# stm32h750xbh6-sig.net
KiCad netlist of a schematic drawn in Altium Designer
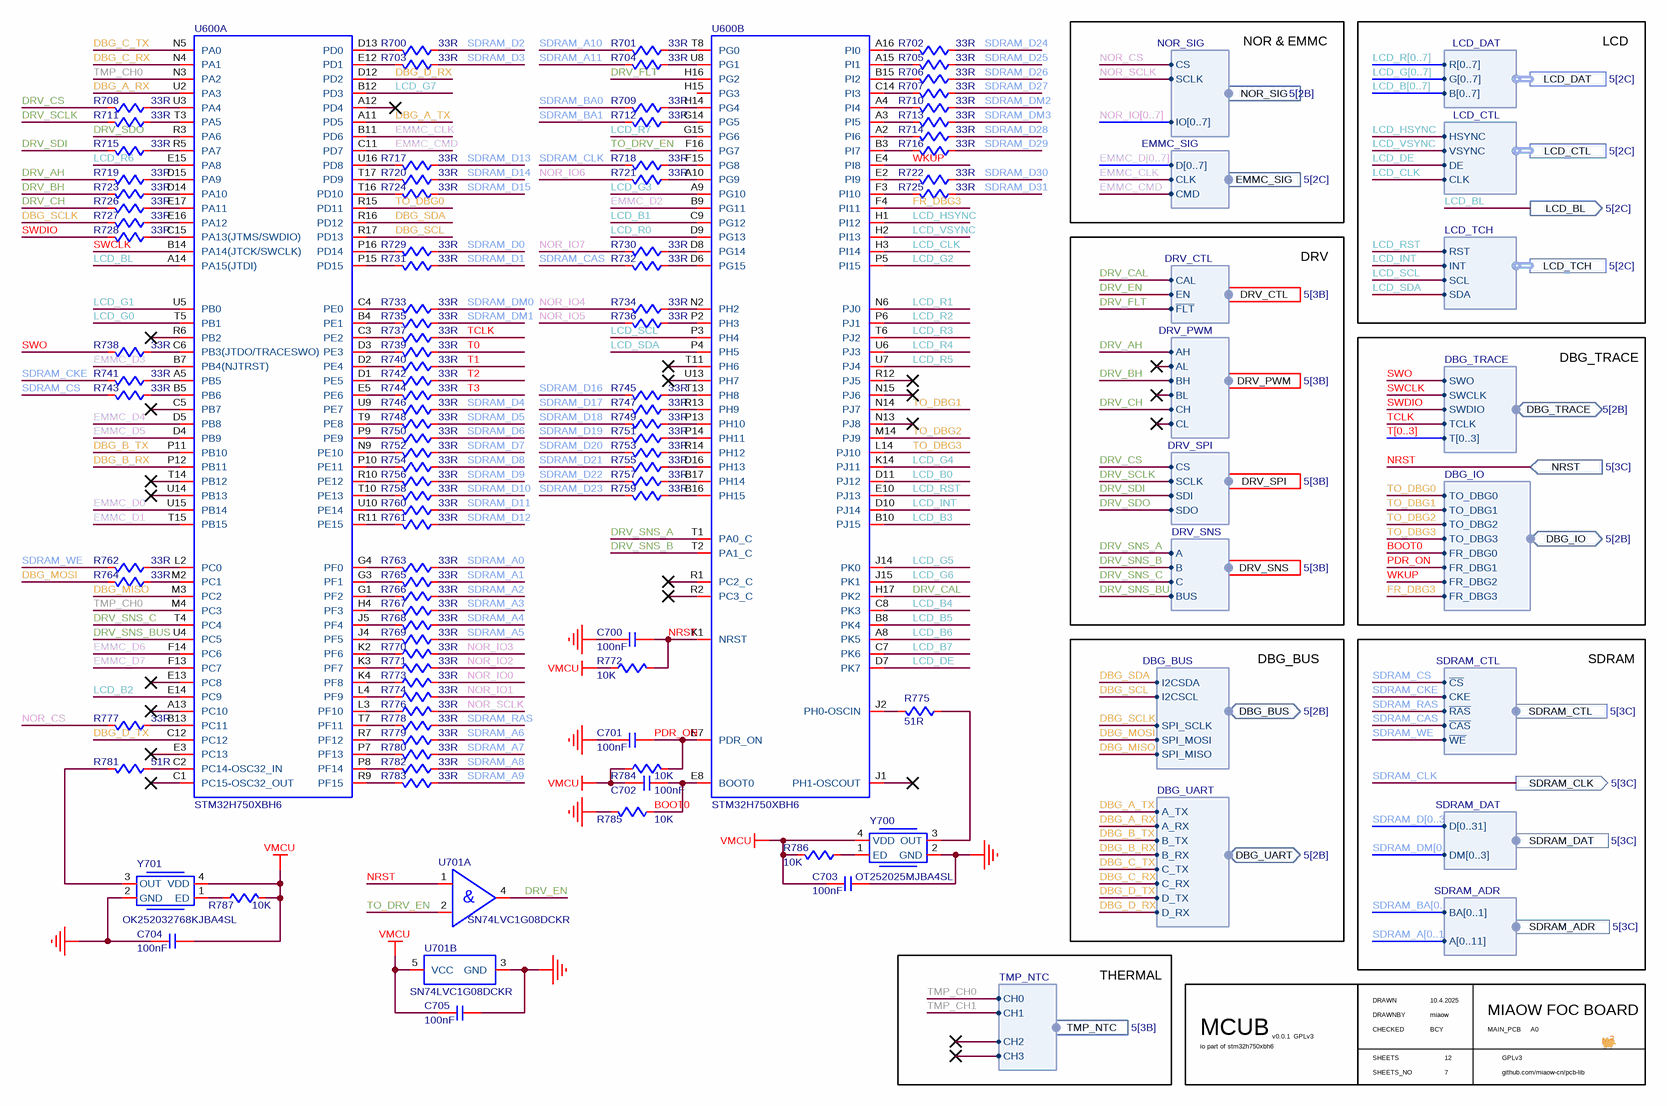
[diagram p0: stm32h750xbh6-sig.SchDoc]

(export (version "E")
  (design (tool "Eeschema 10.0.6"))
  (components
    (comp (ref "C700")
      (value "100nF")
      (footprint "mw:C0402")
      (fields (field (name "VOLTAGE") "25V") (field (name "Comment") "C-NOMO"))
      (libsource (lib "mw") (part "C-NOMO"))
    )
    (comp (ref "C701")
      (value "100nF")
      (footprint "mw:C0402")
      (fields (field (name "VOLTAGE") "25V") (field (name "Comment") "C-NOMO"))
      (libsource (lib "mw") (part "C-NOMO"))
    )
    (comp (ref "C702")
      (value "100nF")
      (footprint "mw:C0402")
      (fields (field (name "VOLTAGE") "25V") (field (name "Comment") "C-NOMO"))
      (libsource (lib "mw") (part "C-NOMO"))
    )
    (comp (ref "C703")
      (value "100nF")
      (footprint "mw:C0402")
      (fields (field (name "VOLTAGE") "25V") (field (name "Comment") "C-NOMO"))
      (libsource (lib "mw") (part "C-NOMO"))
    )
    (comp (ref "C704")
      (value "100nF")
      (footprint "mw:C0402")
      (fields (field (name "VOLTAGE") "25V") (field (name "Comment") "C-NOMO"))
      (libsource (lib "mw") (part "C-NOMO"))
    )
    (comp (ref "C705")
      (value "100nF")
      (footprint "mw:C0402")
      (fields (field (name "VOLTAGE") "25V") (field (name "Comment") "C-NOMO"))
      (libsource (lib "mw") (part "C-NOMO"))
    )
    (comp (ref "R700")
      (value "33R")
      (footprint "mw:R0402")
      (fields (field (name "Comment") "R"))
      (libsource (lib "mw") (part "R"))
    )
    (comp (ref "R701")
      (value "33R")
      (footprint "mw:R0402")
      (fields (field (name "Comment") "R"))
      (libsource (lib "mw") (part "R"))
    )
    (comp (ref "R702")
      (value "33R")
      (footprint "mw:R0402")
      (fields (field (name "Comment") "R"))
      (libsource (lib "mw") (part "R"))
    )
    (comp (ref "R703")
      (value "33R")
      (footprint "mw:R0402")
      (fields (field (name "Comment") "R"))
      (libsource (lib "mw") (part "R"))
    )
    (comp (ref "R704")
      (value "33R")
      (footprint "mw:R0402")
      (fields (field (name "Comment") "R"))
      (libsource (lib "mw") (part "R"))
    )
    (comp (ref "R705")
      (value "33R")
      (footprint "mw:R0402")
      (fields (field (name "Comment") "R"))
      (libsource (lib "mw") (part "R"))
    )
    (comp (ref "R706")
      (value "33R")
      (footprint "mw:R0402")
      (fields (field (name "Comment") "R"))
      (libsource (lib "mw") (part "R"))
    )
    (comp (ref "R707")
      (value "33R")
      (footprint "mw:R0402")
      (fields (field (name "Comment") "R"))
      (libsource (lib "mw") (part "R"))
    )
    (comp (ref "R708")
      (value "33R")
      (footprint "mw:R0402")
      (fields (field (name "Comment") "R"))
      (libsource (lib "mw") (part "R"))
    )
    (comp (ref "R709")
      (value "33R")
      (footprint "mw:R0402")
      (fields (field (name "Comment") "R"))
      (libsource (lib "mw") (part "R"))
    )
    (comp (ref "R710")
      (value "33R")
      (footprint "mw:R0402")
      (fields (field (name "Comment") "R"))
      (libsource (lib "mw") (part "R"))
    )
    (comp (ref "R711")
      (value "33R")
      (footprint "mw:R0402")
      (fields (field (name "Comment") "R"))
      (libsource (lib "mw") (part "R"))
    )
    (comp (ref "R712")
      (value "33R")
      (footprint "mw:R0402")
      (fields (field (name "Comment") "R"))
      (libsource (lib "mw") (part "R"))
    )
    (comp (ref "R713")
      (value "33R")
      (footprint "mw:R0402")
      (fields (field (name "Comment") "R"))
      (libsource (lib "mw") (part "R"))
    )
    (comp (ref "R714")
      (value "33R")
      (footprint "mw:R0402")
      (fields (field (name "Comment") "R"))
      (libsource (lib "mw") (part "R"))
    )
    (comp (ref "R715")
      (value "33R")
      (footprint "mw:R0402")
      (fields (field (name "Comment") "R"))
      (libsource (lib "mw") (part "R"))
    )
    (comp (ref "R716")
      (value "33R")
      (footprint "mw:R0402")
      (fields (field (name "Comment") "R"))
      (libsource (lib "mw") (part "R"))
    )
    (comp (ref "R717")
      (value "33R")
      (footprint "mw:R0402")
      (fields (field (name "Comment") "R"))
      (libsource (lib "mw") (part "R"))
    )
    (comp (ref "R718")
      (value "33R")
      (footprint "mw:R0402")
      (fields (field (name "Comment") "R"))
      (libsource (lib "mw") (part "R"))
    )
    (comp (ref "R719")
      (value "33R")
      (footprint "mw:R0402")
      (fields (field (name "Comment") "R"))
      (libsource (lib "mw") (part "R"))
    )
    (comp (ref "R720")
      (value "33R")
      (footprint "mw:R0402")
      (fields (field (name "Comment") "R"))
      (libsource (lib "mw") (part "R"))
    )
    (comp (ref "R721")
      (value "33R")
      (footprint "mw:R0402")
      (fields (field (name "Comment") "R"))
      (libsource (lib "mw") (part "R"))
    )
    (comp (ref "R722")
      (value "33R")
      (footprint "mw:R0402")
      (fields (field (name "Comment") "R"))
      (libsource (lib "mw") (part "R"))
    )
    (comp (ref "R723")
      (value "33R")
      (footprint "mw:R0402")
      (fields (field (name "Comment") "R"))
      (libsource (lib "mw") (part "R"))
    )
    (comp (ref "R724")
      (value "33R")
      (footprint "mw:R0402")
      (fields (field (name "Comment") "R"))
      (libsource (lib "mw") (part "R"))
    )
    (comp (ref "R725")
      (value "33R")
      (footprint "mw:R0402")
      (fields (field (name "Comment") "R"))
      (libsource (lib "mw") (part "R"))
    )
    (comp (ref "R726")
      (value "33R")
      (footprint "mw:R0402")
      (fields (field (name "Comment") "R"))
      (libsource (lib "mw") (part "R"))
    )
    (comp (ref "R727")
      (value "33R")
      (footprint "mw:R0402")
      (fields (field (name "Comment") "R"))
      (libsource (lib "mw") (part "R"))
    )
    (comp (ref "R728")
      (value "33R")
      (footprint "mw:R0402")
      (fields (field (name "Comment") "R"))
      (libsource (lib "mw") (part "R"))
    )
    (comp (ref "R729")
      (value "33R")
      (footprint "mw:R0402")
      (fields (field (name "Comment") "R"))
      (libsource (lib "mw") (part "R"))
    )
    (comp (ref "R730")
      (value "33R")
      (footprint "mw:R0402")
      (fields (field (name "Comment") "R"))
      (libsource (lib "mw") (part "R"))
    )
    (comp (ref "R731")
      (value "33R")
      (footprint "mw:R0402")
      (fields (field (name "Comment") "R"))
      (libsource (lib "mw") (part "R"))
    )
    (comp (ref "R732")
      (value "33R")
      (footprint "mw:R0402")
      (fields (field (name "Comment") "R"))
      (libsource (lib "mw") (part "R"))
    )
    (comp (ref "R733")
      (value "33R")
      (footprint "mw:R0402")
      (fields (field (name "Comment") "R"))
      (libsource (lib "mw") (part "R"))
    )
    (comp (ref "R734")
      (value "33R")
      (footprint "mw:R0402")
      (fields (field (name "Comment") "R"))
      (libsource (lib "mw") (part "R"))
    )
    (comp (ref "R735")
      (value "33R")
      (footprint "mw:R0402")
      (fields (field (name "Comment") "R"))
      (libsource (lib "mw") (part "R"))
    )
    (comp (ref "R736")
      (value "33R")
      (footprint "mw:R0402")
      (fields (field (name "Comment") "R"))
      (libsource (lib "mw") (part "R"))
    )
    (comp (ref "R737")
      (value "33R")
      (footprint "mw:R0402")
      (fields (field (name "Comment") "R"))
      (libsource (lib "mw") (part "R"))
    )
    (comp (ref "R738")
      (value "33R")
      (footprint "mw:R0402")
      (fields (field (name "Comment") "R"))
      (libsource (lib "mw") (part "R"))
    )
    (comp (ref "R739")
      (value "33R")
      (footprint "mw:R0402")
      (fields (field (name "Comment") "R"))
      (libsource (lib "mw") (part "R"))
    )
    (comp (ref "R740")
      (value "33R")
      (footprint "mw:R0402")
      (fields (field (name "Comment") "R"))
      (libsource (lib "mw") (part "R"))
    )
    (comp (ref "R741")
      (value "33R")
      (footprint "mw:R0402")
      (fields (field (name "Comment") "R"))
      (libsource (lib "mw") (part "R"))
    )
    (comp (ref "R742")
      (value "33R")
      (footprint "mw:R0402")
      (fields (field (name "Comment") "R"))
      (libsource (lib "mw") (part "R"))
    )
    (comp (ref "R743")
      (value "33R")
      (footprint "mw:R0402")
      (fields (field (name "Comment") "R"))
      (libsource (lib "mw") (part "R"))
    )
    (comp (ref "R744")
      (value "33R")
      (footprint "mw:R0402")
      (fields (field (name "Comment") "R"))
      (libsource (lib "mw") (part "R"))
    )
    (comp (ref "R745")
      (value "33R")
      (footprint "mw:R0402")
      (fields (field (name "Comment") "R"))
      (libsource (lib "mw") (part "R"))
    )
    (comp (ref "R746")
      (value "33R")
      (footprint "mw:R0402")
      (fields (field (name "Comment") "R"))
      (libsource (lib "mw") (part "R"))
    )
    (comp (ref "R747")
      (value "33R")
      (footprint "mw:R0402")
      (fields (field (name "Comment") "R"))
      (libsource (lib "mw") (part "R"))
    )
    (comp (ref "R748")
      (value "33R")
      (footprint "mw:R0402")
      (fields (field (name "Comment") "R"))
      (libsource (lib "mw") (part "R"))
    )
    (comp (ref "R749")
      (value "33R")
      (footprint "mw:R0402")
      (fields (field (name "Comment") "R"))
      (libsource (lib "mw") (part "R"))
    )
    (comp (ref "R750")
      (value "33R")
      (footprint "mw:R0402")
      (fields (field (name "Comment") "R"))
      (libsource (lib "mw") (part "R"))
    )
    (comp (ref "R751")
      (value "33R")
      (footprint "mw:R0402")
      (fields (field (name "Comment") "R"))
      (libsource (lib "mw") (part "R"))
    )
    (comp (ref "R752")
      (value "33R")
      (footprint "mw:R0402")
      (fields (field (name "Comment") "R"))
      (libsource (lib "mw") (part "R"))
    )
    (comp (ref "R753")
      (value "33R")
      (footprint "mw:R0402")
      (fields (field (name "Comment") "R"))
      (libsource (lib "mw") (part "R"))
    )
    (comp (ref "R754")
      (value "33R")
      (footprint "mw:R0402")
      (fields (field (name "Comment") "R"))
      (libsource (lib "mw") (part "R"))
    )
    (comp (ref "R755")
      (value "33R")
      (footprint "mw:R0402")
      (fields (field (name "Comment") "R"))
      (libsource (lib "mw") (part "R"))
    )
    (comp (ref "R756")
      (value "33R")
      (footprint "mw:R0402")
      (fields (field (name "Comment") "R"))
      (libsource (lib "mw") (part "R"))
    )
    (comp (ref "R757")
      (value "33R")
      (footprint "mw:R0402")
      (fields (field (name "Comment") "R"))
      (libsource (lib "mw") (part "R"))
    )
    (comp (ref "R758")
      (value "33R")
      (footprint "mw:R0402")
      (fields (field (name "Comment") "R"))
      (libsource (lib "mw") (part "R"))
    )
    (comp (ref "R759")
      (value "33R")
      (footprint "mw:R0402")
      (fields (field (name "Comment") "R"))
      (libsource (lib "mw") (part "R"))
    )
    (comp (ref "R760")
      (value "33R")
      (footprint "mw:R0402")
      (fields (field (name "Comment") "R"))
      (libsource (lib "mw") (part "R"))
    )
    (comp (ref "R761")
      (value "33R")
      (footprint "mw:R0402")
      (fields (field (name "Comment") "R"))
      (libsource (lib "mw") (part "R"))
    )
    (comp (ref "R762")
      (value "33R")
      (footprint "mw:R0402")
      (fields (field (name "Comment") "R"))
      (libsource (lib "mw") (part "R"))
    )
    (comp (ref "R763")
      (value "33R")
      (footprint "mw:R0402")
      (fields (field (name "Comment") "R"))
      (libsource (lib "mw") (part "R"))
    )
    (comp (ref "R764")
      (value "33R")
      (footprint "mw:R0402")
      (fields (field (name "Comment") "R"))
      (libsource (lib "mw") (part "R"))
    )
    (comp (ref "R765")
      (value "33R")
      (footprint "mw:R0402")
      (fields (field (name "Comment") "R"))
      (libsource (lib "mw") (part "R"))
    )
    (comp (ref "R766")
      (value "33R")
      (footprint "mw:R0402")
      (fields (field (name "Comment") "R"))
      (libsource (lib "mw") (part "R"))
    )
    (comp (ref "R767")
      (value "33R")
      (footprint "mw:R0402")
      (fields (field (name "Comment") "R"))
      (libsource (lib "mw") (part "R"))
    )
    (comp (ref "R768")
      (value "33R")
      (footprint "mw:R0402")
      (fields (field (name "Comment") "R"))
      (libsource (lib "mw") (part "R"))
    )
    (comp (ref "R769")
      (value "33R")
      (footprint "mw:R0402")
      (fields (field (name "Comment") "R"))
      (libsource (lib "mw") (part "R"))
    )
    (comp (ref "R770")
      (value "33R")
      (footprint "mw:R0402")
      (fields (field (name "Comment") "R"))
      (libsource (lib "mw") (part "R"))
    )
    (comp (ref "R771")
      (value "33R")
      (footprint "mw:R0402")
      (fields (field (name "Comment") "R"))
      (libsource (lib "mw") (part "R"))
    )
    (comp (ref "R772")
      (value "10K")
      (footprint "mw:R0402")
      (fields (field (name "Comment") "R"))
      (libsource (lib "mw") (part "R"))
    )
    (comp (ref "R773")
      (value "33R")
      (footprint "mw:R0402")
      (fields (field (name "Comment") "R"))
      (libsource (lib "mw") (part "R"))
    )
    (comp (ref "R774")
      (value "33R")
      (footprint "mw:R0402")
      (fields (field (name "Comment") "R"))
      (libsource (lib "mw") (part "R"))
    )
    (comp (ref "R775")
      (value "51R")
      (footprint "mw:R0402")
      (fields (field (name "Comment") "R"))
      (libsource (lib "mw") (part "R"))
    )
    (comp (ref "R776")
      (value "33R")
      (footprint "mw:R0402")
      (fields (field (name "Comment") "R"))
      (libsource (lib "mw") (part "R"))
    )
    (comp (ref "R777")
      (value "33R")
      (footprint "mw:R0402")
      (fields (field (name "Comment") "R"))
      (libsource (lib "mw") (part "R"))
    )
    (comp (ref "R778")
      (value "33R")
      (footprint "mw:R0402")
      (fields (field (name "Comment") "R"))
      (libsource (lib "mw") (part "R"))
    )
    (comp (ref "R779")
      (value "33R")
      (footprint "mw:R0402")
      (fields (field (name "Comment") "R"))
      (libsource (lib "mw") (part "R"))
    )
    (comp (ref "R780")
      (value "33R")
      (footprint "mw:R0402")
      (fields (field (name "Comment") "R"))
      (libsource (lib "mw") (part "R"))
    )
    (comp (ref "R781")
      (value "51R")
      (footprint "mw:R0402")
      (fields (field (name "Comment") "R"))
      (libsource (lib "mw") (part "R"))
    )
    (comp (ref "R782")
      (value "33R")
      (footprint "mw:R0402")
      (fields (field (name "Comment") "R"))
      (libsource (lib "mw") (part "R"))
    )
    (comp (ref "R783")
      (value "33R")
      (footprint "mw:R0402")
      (fields (field (name "Comment") "R"))
      (libsource (lib "mw") (part "R"))
    )
    (comp (ref "R784")
      (value "10K")
      (footprint "mw:R0402")
      (fields (field (name "Comment") "R"))
      (libsource (lib "mw") (part "R"))
    )
    (comp (ref "R785")
      (value "10K")
      (footprint "mw:R0402")
      (fields (field (name "Comment") "R"))
      (libsource (lib "mw") (part "R"))
    )
    (comp (ref "R786")
      (value "10K")
      (footprint "mw:R0402")
      (fields (field (name "Comment") "R"))
      (libsource (lib "mw") (part "R"))
    )
    (comp (ref "R787")
      (value "10K")
      (footprint "mw:R0402")
      (fields (field (name "Comment") "R"))
      (libsource (lib "mw") (part "R"))
    )
    (comp (ref "U600")
      (value "STM32H750XBH6")
      (footprint "mw:STM32H750XBH6")
      (description "MCU")
      (libsource (lib "mw") (part "STM32H750XBH6"))
    )
    (comp (ref "U701")
      (value "SN74LVC1G08DCKR")
      (footprint "mw:SN74LVC1G08DCKR")
      (description "AND GATE  - 1bit")
      (libsource (lib "mw") (part "SN74LVC1G08DCKR"))
    )
    (comp (ref "Y700")
      (value "OT252025MJBA4SL")
      (footprint "mw:OT252025MJBA4SL")
      (libsource (lib "mw") (part "OT252025MJBA4SL"))
    )
    (comp (ref "Y701")
      (value "OK252032768KJBA4SL")
      (footprint "mw:OK252032768KJBA4SL")
      (libsource (lib "mw") (part "OK252032768KJBA4SL"))
    )
  )
  (nets
    (net (code "18") (name "/BOOT0") (class "Default")
      (node (ref "C702") (pin "1") (pinfunction "1_1") (pintype "passive"))
      (node (ref "R785") (pin "2") (pinfunction "2_2") (pintype "passive"))
      (node (ref "U600") (pin "E8") (pinfunction "BOOT0_E8") (pintype "passive"))
    )
    (net (code "19") (name "/DBG_A_RX") (class "Default")
      (node (ref "U600") (pin "U2") (pinfunction "PA3_U2") (pintype "passive"))
    )
    (net (code "20") (name "/DBG_A_TX") (class "Default")
      (node (ref "U600") (pin "A11") (pinfunction "PD5_A11") (pintype "passive"))
    )
    (net (code "21") (name "/DBG_B_RX") (class "Default")
      (node (ref "U600") (pin "P12") (pinfunction "PB11_P12") (pintype "passive"))
    )
    (net (code "22") (name "/DBG_B_TX") (class "Default")
      (node (ref "U600") (pin "P11") (pinfunction "PB10_P11") (pintype "passive"))
    )
    (net (code "23") (name "/DBG_C_RX") (class "Default")
      (node (ref "U600") (pin "N4") (pinfunction "PA1_N4") (pintype "passive"))
    )
    (net (code "24") (name "/DBG_C_TX") (class "Default")
      (node (ref "U600") (pin "N5") (pinfunction "PA0_N5") (pintype "passive"))
    )
    (net (code "25") (name "/DBG_D_RX") (class "Default")
      (node (ref "U600") (pin "D12") (pinfunction "PD2_D12") (pintype "passive"))
    )
    (net (code "26") (name "/DBG_D_TX") (class "Default")
      (node (ref "U600") (pin "C12") (pinfunction "PC12_C12") (pintype "passive"))
    )
    (net (code "27") (name "/DBG_MISO") (class "Default")
      (node (ref "U600") (pin "M3") (pinfunction "PC2_M3") (pintype "passive"))
    )
    (net (code "28") (name "/DBG_MOSI") (class "Default")
      (node (ref "R764") (pin "2") (pinfunction "2_2") (pintype "passive"))
    )
    (net (code "29") (name "/DBG_SCL") (class "Default")
      (node (ref "U600") (pin "R17") (pinfunction "PD13_R17") (pintype "passive"))
    )
    (net (code "30") (name "/DBG_SCLK") (class "Default")
      (node (ref "R727") (pin "2") (pinfunction "2_2") (pintype "passive"))
    )
    (net (code "31") (name "/DBG_SDA") (class "Default")
      (node (ref "U600") (pin "R16") (pinfunction "PD12_R16") (pintype "passive"))
    )
    (net (code "33") (name "/DRV_AH") (class "Default")
      (node (ref "R719") (pin "2") (pinfunction "2_2") (pintype "passive"))
    )
    (net (code "34") (name "/DRV_BH") (class "Default")
      (node (ref "R723") (pin "2") (pinfunction "2_2") (pintype "passive"))
    )
    (net (code "35") (name "/DRV_CAL") (class "Default")
      (node (ref "U600") (pin "H17") (pinfunction "PK2_H17") (pintype "passive"))
    )
    (net (code "36") (name "/DRV_CH") (class "Default")
      (node (ref "R726") (pin "2") (pinfunction "2_2") (pintype "passive"))
    )
    (net (code "37") (name "/DRV_CS") (class "Default")
      (node (ref "R708") (pin "2") (pinfunction "2_2") (pintype "passive"))
    )
    (net (code "38") (name "/DRV_EN") (class "Default")
      (node (ref "U701") (pin "4") (pinfunction "Y_4") (pintype "passive"))
    )
    (net (code "39") (name "/DRV_FLT") (class "Default")
      (node (ref "U600") (pin "H16") (pinfunction "PG2_H16") (pintype "passive"))
    )
    (net (code "40") (name "/DRV_SCLK") (class "Default")
      (node (ref "R711") (pin "2") (pinfunction "2_2") (pintype "passive"))
    )
    (net (code "41") (name "/DRV_SDI") (class "Default")
      (node (ref "R715") (pin "2") (pinfunction "2_2") (pintype "passive"))
    )
    (net (code "42") (name "/DRV_SDO") (class "Default")
      (node (ref "U600") (pin "R3") (pinfunction "PA6_R3") (pintype "passive"))
    )
    (net (code "43") (name "/DRV_SNS_A") (class "Default")
      (node (ref "U600") (pin "T1") (pinfunction "PA0_C_T1") (pintype "passive"))
    )
    (net (code "44") (name "/DRV_SNS_B") (class "Default")
      (node (ref "U600") (pin "T2") (pinfunction "PA1_C_T2") (pintype "passive"))
    )
    (net (code "45") (name "/DRV_SNS_BUS") (class "Default")
      (node (ref "U600") (pin "U4") (pinfunction "PC5_U4") (pintype "passive"))
    )
    (net (code "46") (name "/DRV_SNS_C") (class "Default")
      (node (ref "U600") (pin "T4") (pinfunction "PC4_T4") (pintype "passive"))
    )
    (net (code "47") (name "/EMMC_CLK") (class "Default")
      (node (ref "U600") (pin "B11") (pinfunction "PD6_B11") (pintype "passive"))
    )
    (net (code "48") (name "/EMMC_CMD") (class "Default")
      (node (ref "U600") (pin "C11") (pinfunction "PD7_C11") (pintype "passive"))
    )
    (net (code "49") (name "/EMMC_D0") (class "Default")
      (node (ref "U600") (pin "U15") (pinfunction "PB14_U15") (pintype "passive"))
    )
    (net (code "50") (name "/EMMC_D1") (class "Default")
      (node (ref "U600") (pin "T15") (pinfunction "PB15_T15") (pintype "passive"))
    )
    (net (code "51") (name "/EMMC_D2") (class "Default")
      (node (ref "U600") (pin "B9") (pinfunction "PG11_B9") (pintype "passive"))
    )
    (net (code "52") (name "/EMMC_D3") (class "Default")
      (node (ref "U600") (pin "B7") (pinfunction "PB4(NJTRST)_B7") (pintype "passive"))
    )
    (net (code "53") (name "/EMMC_D4") (class "Default")
      (node (ref "U600") (pin "D5") (pinfunction "PB8_D5") (pintype "passive"))
    )
    (net (code "54") (name "/EMMC_D5") (class "Default")
      (node (ref "U600") (pin "D4") (pinfunction "PB9_D4") (pintype "passive"))
    )
    (net (code "55") (name "/EMMC_D6") (class "Default")
      (node (ref "U600") (pin "F14") (pinfunction "PC6_F14") (pintype "passive"))
    )
    (net (code "56") (name "/EMMC_D7") (class "Default")
      (node (ref "U600") (pin "F13") (pinfunction "PC7_F13") (pintype "passive"))
    )
    (net (code "58") (name "/FR_DBG3") (class "Default")
      (node (ref "U600") (pin "F4") (pinfunction "PI11_F4") (pintype "passive"))
    )
    (net (code "59") (name "/LCD_B0") (class "Default")
      (node (ref "U600") (pin "D11") (pinfunction "PJ12_D11") (pintype "passive"))
    )
    (net (code "60") (name "/LCD_B1") (class "Default")
      (node (ref "U600") (pin "C9") (pinfunction "PG12_C9") (pintype "passive"))
    )
    (net (code "61") (name "/LCD_B2") (class "Default")
      (node (ref "U600") (pin "E14") (pinfunction "PC9_E14") (pintype "passive"))
    )
    (net (code "62") (name "/LCD_B3") (class "Default")
      (node (ref "U600") (pin "B10") (pinfunction "PJ15_B10") (pintype "passive"))
    )
    (net (code "63") (name "/LCD_B4") (class "Default")
      (node (ref "U600") (pin "C8") (pinfunction "PK3_C8") (pintype "passive"))
    )
    (net (code "64") (name "/LCD_B5") (class "Default")
      (node (ref "U600") (pin "B8") (pinfunction "PK4_B8") (pintype "passive"))
    )
    (net (code "65") (name "/LCD_B6") (class "Default")
      (node (ref "U600") (pin "A8") (pinfunction "PK5_A8") (pintype "passive"))
    )
    (net (code "66") (name "/LCD_B7") (class "Default")
      (node (ref "U600") (pin "C7") (pinfunction "PK6_C7") (pintype "passive"))
    )
    (net (code "67") (name "/LCD_BL") (class "Default")
      (node (ref "U600") (pin "A14") (pinfunction "PA15(JTDI)_A14") (pintype "passive"))
    )
    (net (code "68") (name "/LCD_CLK") (class "Default")
      (node (ref "U600") (pin "H3") (pinfunction "PI14_H3") (pintype "passive"))
    )
    (net (code "70") (name "/LCD_DE") (class "Default")
      (node (ref "U600") (pin "D7") (pinfunction "PK7_D7") (pintype "passive"))
    )
    (net (code "71") (name "/LCD_G0") (class "Default")
      (node (ref "U600") (pin "T5") (pinfunction "PB1_T5") (pintype "passive"))
    )
    (net (code "72") (name "/LCD_G1") (class "Default")
      (node (ref "U600") (pin "U5") (pinfunction "PB0_U5") (pintype "passive"))
    )
    (net (code "73") (name "/LCD_G2") (class "Default")
      (node (ref "U600") (pin "P5") (pinfunction "PI15_P5") (pintype "passive"))
    )
    (net (code "74") (name "/LCD_G3") (class "Default")
      (node (ref "U600") (pin "A9") (pinfunction "PG10_A9") (pintype "passive"))
    )
    (net (code "75") (name "/LCD_G4") (class "Default")
      (node (ref "U600") (pin "K14") (pinfunction "PJ11_K14") (pintype "passive"))
    )
    (net (code "76") (name "/LCD_G5") (class "Default")
      (node (ref "U600") (pin "J14") (pinfunction "PK0_J14") (pintype "passive"))
    )
    (net (code "77") (name "/LCD_G6") (class "Default")
      (node (ref "U600") (pin "J15") (pinfunction "PK1_J15") (pintype "passive"))
    )
    (net (code "78") (name "/LCD_G7") (class "Default")
      (node (ref "U600") (pin "B12") (pinfunction "PD3_B12") (pintype "passive"))
    )
    (net (code "80") (name "/LCD_HSYNC") (class "Default")
      (node (ref "U600") (pin "H1") (pinfunction "PI12_H1") (pintype "passive"))
    )
    (net (code "81") (name "/LCD_INT") (class "Default")
      (node (ref "U600") (pin "D10") (pinfunction "PJ14_D10") (pintype "passive"))
    )
    (net (code "82") (name "/LCD_R0") (class "Default")
      (node (ref "U600") (pin "D9") (pinfunction "PG13_D9") (pintype "passive"))
    )
    (net (code "83") (name "/LCD_R1") (class "Default")
      (node (ref "U600") (pin "N6") (pinfunction "PJ0_N6") (pintype "passive"))
    )
    (net (code "84") (name "/LCD_R2") (class "Default")
      (node (ref "U600") (pin "P6") (pinfunction "PJ1_P6") (pintype "passive"))
    )
    (net (code "85") (name "/LCD_R3") (class "Default")
      (node (ref "U600") (pin "T6") (pinfunction "PJ2_T6") (pintype "passive"))
    )
    (net (code "86") (name "/LCD_R4") (class "Default")
      (node (ref "U600") (pin "U6") (pinfunction "PJ3_U6") (pintype "passive"))
    )
    (net (code "87") (name "/LCD_R5") (class "Default")
      (node (ref "U600") (pin "U7") (pinfunction "PJ4_U7") (pintype "passive"))
    )
    (net (code "88") (name "/LCD_R6") (class "Default")
      (node (ref "U600") (pin "E15") (pinfunction "PA8_E15") (pintype "passive"))
    )
    (net (code "89") (name "/LCD_R7") (class "Default")
      (node (ref "U600") (pin "G15") (pinfunction "PG6_G15") (pintype "passive"))
    )
    (net (code "90") (name "/LCD_RST") (class "Default")
      (node (ref "U600") (pin "E10") (pinfunction "PJ13_E10") (pintype "passive"))
    )
    (net (code "92") (name "/LCD_SCL") (class "Default")
      (node (ref "U600") (pin "P3") (pinfunction "PH4_P3") (pintype "passive"))
    )
    (net (code "93") (name "/LCD_SDA") (class "Default")
      (node (ref "U600") (pin "P4") (pinfunction "PH5_P4") (pintype "passive"))
    )
    (net (code "94") (name "/LCD_VSYNC") (class "Default")
      (node (ref "U600") (pin "H2") (pinfunction "PI13_H2") (pintype "passive"))
    )
    (net (code "95") (name "/NOR_CS") (class "Default")
      (node (ref "R777") (pin "2") (pinfunction "2_2") (pintype "passive"))
    )
    (net (code "96") (name "/NOR_IO0") (class "Default")
      (node (ref "R773") (pin "2") (pinfunction "2_2") (pintype "passive"))
    )
    (net (code "97") (name "/NOR_IO1") (class "Default")
      (node (ref "R774") (pin "2") (pinfunction "2_2") (pintype "passive"))
    )
    (net (code "98") (name "/NOR_IO2") (class "Default")
      (node (ref "R771") (pin "2") (pinfunction "2_2") (pintype "passive"))
    )
    (net (code "99") (name "/NOR_IO3") (class "Default")
      (node (ref "R770") (pin "2") (pinfunction "2_2") (pintype "passive"))
    )
    (net (code "100") (name "/NOR_IO4") (class "Default")
      (node (ref "R734") (pin "2") (pinfunction "2_2") (pintype "passive"))
    )
    (net (code "101") (name "/NOR_IO5") (class "Default")
      (node (ref "R736") (pin "2") (pinfunction "2_2") (pintype "passive"))
    )
    (net (code "102") (name "/NOR_IO6") (class "Default")
      (node (ref "R721") (pin "2") (pinfunction "2_2") (pintype "passive"))
    )
    (net (code "103") (name "/NOR_IO7") (class "Default")
      (node (ref "R730") (pin "2") (pinfunction "2_2") (pintype "passive"))
    )
    (net (code "104") (name "/NOR_SCLK") (class "Default")
      (node (ref "R776") (pin "2") (pinfunction "2_2") (pintype "passive"))
    )
    (net (code "106") (name "/NRST") (class "Default")
      (node (ref "C700") (pin "1") (pinfunction "1_1") (pintype "passive"))
      (node (ref "R772") (pin "2") (pinfunction "2_2") (pintype "passive"))
      (node (ref "U600") (pin "K1") (pinfunction "NRST_K1") (pintype "passive"))
      (node (ref "U701") (pin "1") (pinfunction "A_1") (pintype "passive"))
    )
    (net (code "107") (name "/PDR_ON") (class "Default")
      (node (ref "C701") (pin "1") (pinfunction "1_1") (pintype "passive"))
      (node (ref "R784") (pin "1") (pinfunction "1_1") (pintype "passive"))
      (node (ref "U600") (pin "E7") (pinfunction "PDR_ON_E7") (pintype "passive"))
    )
    (net (code "108") (name "/SDRAM_A0") (class "Default")
      (node (ref "R763") (pin "2") (pinfunction "2_2") (pintype "passive"))
    )
    (net (code "109") (name "/SDRAM_A1") (class "Default")
      (node (ref "R765") (pin "2") (pinfunction "2_2") (pintype "passive"))
    )
    (net (code "110") (name "/SDRAM_A2") (class "Default")
      (node (ref "R766") (pin "2") (pinfunction "2_2") (pintype "passive"))
    )
    (net (code "111") (name "/SDRAM_A3") (class "Default")
      (node (ref "R767") (pin "2") (pinfunction "2_2") (pintype "passive"))
    )
    (net (code "112") (name "/SDRAM_A4") (class "Default")
      (node (ref "R768") (pin "2") (pinfunction "2_2") (pintype "passive"))
    )
    (net (code "113") (name "/SDRAM_A5") (class "Default")
      (node (ref "R769") (pin "2") (pinfunction "2_2") (pintype "passive"))
    )
    (net (code "114") (name "/SDRAM_A6") (class "Default")
      (node (ref "R779") (pin "2") (pinfunction "2_2") (pintype "passive"))
    )
    (net (code "115") (name "/SDRAM_A7") (class "Default")
      (node (ref "R780") (pin "2") (pinfunction "2_2") (pintype "passive"))
    )
    (net (code "116") (name "/SDRAM_A8") (class "Default")
      (node (ref "R782") (pin "2") (pinfunction "2_2") (pintype "passive"))
    )
    (net (code "117") (name "/SDRAM_A9") (class "Default")
      (node (ref "R783") (pin "2") (pinfunction "2_2") (pintype "passive"))
    )
    (net (code "118") (name "/SDRAM_A10") (class "Default")
      (node (ref "R701") (pin "2") (pinfunction "2_2") (pintype "passive"))
    )
    (net (code "119") (name "/SDRAM_A11") (class "Default")
      (node (ref "R704") (pin "2") (pinfunction "2_2") (pintype "passive"))
    )
    (net (code "121") (name "/SDRAM_BA0") (class "Default")
      (node (ref "R709") (pin "2") (pinfunction "2_2") (pintype "passive"))
    )
    (net (code "122") (name "/SDRAM_BA1") (class "Default")
      (node (ref "R712") (pin "2") (pinfunction "2_2") (pintype "passive"))
    )
    (net (code "124") (name "/SDRAM_CAS") (class "Default")
      (node (ref "R732") (pin "2") (pinfunction "2_2") (pintype "passive"))
    )
    (net (code "125") (name "/SDRAM_CKE") (class "Default")
      (node (ref "R741") (pin "2") (pinfunction "2_2") (pintype "passive"))
    )
    (net (code "126") (name "/SDRAM_CLK") (class "Default")
      (node (ref "R718") (pin "2") (pinfunction "2_2") (pintype "passive"))
    )
    (net (code "127") (name "/SDRAM_CS") (class "Default")
      (node (ref "R743") (pin "2") (pinfunction "2_2") (pintype "passive"))
    )
    (net (code "128") (name "/SDRAM_D0") (class "Default")
      (node (ref "R729") (pin "2") (pinfunction "2_2") (pintype "passive"))
    )
    (net (code "129") (name "/SDRAM_D1") (class "Default")
      (node (ref "R731") (pin "2") (pinfunction "2_2") (pintype "passive"))
    )
    (net (code "130") (name "/SDRAM_D2") (class "Default")
      (node (ref "R700") (pin "2") (pinfunction "2_2") (pintype "passive"))
    )
    (net (code "131") (name "/SDRAM_D3") (class "Default")
      (node (ref "R703") (pin "2") (pinfunction "2_2") (pintype "passive"))
    )
    (net (code "132") (name "/SDRAM_D4") (class "Default")
      (node (ref "R746") (pin "2") (pinfunction "2_2") (pintype "passive"))
    )
    (net (code "133") (name "/SDRAM_D5") (class "Default")
      (node (ref "R748") (pin "2") (pinfunction "2_2") (pintype "passive"))
    )
    (net (code "134") (name "/SDRAM_D6") (class "Default")
      (node (ref "R750") (pin "2") (pinfunction "2_2") (pintype "passive"))
    )
    (net (code "135") (name "/SDRAM_D7") (class "Default")
      (node (ref "R752") (pin "2") (pinfunction "2_2") (pintype "passive"))
    )
    (net (code "136") (name "/SDRAM_D8") (class "Default")
      (node (ref "R754") (pin "2") (pinfunction "2_2") (pintype "passive"))
    )
    (net (code "137") (name "/SDRAM_D9") (class "Default")
      (node (ref "R756") (pin "2") (pinfunction "2_2") (pintype "passive"))
    )
    (net (code "138") (name "/SDRAM_D10") (class "Default")
      (node (ref "R758") (pin "2") (pinfunction "2_2") (pintype "passive"))
    )
    (net (code "139") (name "/SDRAM_D11") (class "Default")
      (node (ref "R760") (pin "2") (pinfunction "2_2") (pintype "passive"))
    )
    (net (code "140") (name "/SDRAM_D12") (class "Default")
      (node (ref "R761") (pin "2") (pinfunction "2_2") (pintype "passive"))
    )
    (net (code "141") (name "/SDRAM_D13") (class "Default")
      (node (ref "R717") (pin "2") (pinfunction "2_2") (pintype "passive"))
    )
    (net (code "142") (name "/SDRAM_D14") (class "Default")
      (node (ref "R720") (pin "2") (pinfunction "2_2") (pintype "passive"))
    )
    (net (code "143") (name "/SDRAM_D15") (class "Default")
      (node (ref "R724") (pin "2") (pinfunction "2_2") (pintype "passive"))
    )
    (net (code "144") (name "/SDRAM_D16") (class "Default")
      (node (ref "R745") (pin "2") (pinfunction "2_2") (pintype "passive"))
    )
    (net (code "145") (name "/SDRAM_D17") (class "Default")
      (node (ref "R747") (pin "2") (pinfunction "2_2") (pintype "passive"))
    )
    (net (code "146") (name "/SDRAM_D18") (class "Default")
      (node (ref "R749") (pin "2") (pinfunction "2_2") (pintype "passive"))
    )
    (net (code "147") (name "/SDRAM_D19") (class "Default")
      (node (ref "R751") (pin "2") (pinfunction "2_2") (pintype "passive"))
    )
    (net (code "148") (name "/SDRAM_D20") (class "Default")
      (node (ref "R753") (pin "2") (pinfunction "2_2") (pintype "passive"))
    )
    (net (code "149") (name "/SDRAM_D21") (class "Default")
      (node (ref "R755") (pin "2") (pinfunction "2_2") (pintype "passive"))
    )
    (net (code "150") (name "/SDRAM_D22") (class "Default")
      (node (ref "R757") (pin "2") (pinfunction "2_2") (pintype "passive"))
    )
    (net (code "151") (name "/SDRAM_D23") (class "Default")
      (node (ref "R759") (pin "2") (pinfunction "2_2") (pintype "passive"))
    )
    (net (code "152") (name "/SDRAM_D24") (class "Default")
      (node (ref "R702") (pin "2") (pinfunction "2_2") (pintype "passive"))
    )
    (net (code "153") (name "/SDRAM_D25") (class "Default")
      (node (ref "R705") (pin "2") (pinfunction "2_2") (pintype "passive"))
    )
    (net (code "154") (name "/SDRAM_D26") (class "Default")
      (node (ref "R706") (pin "2") (pinfunction "2_2") (pintype "passive"))
    )
    (net (code "155") (name "/SDRAM_D27") (class "Default")
      (node (ref "R707") (pin "2") (pinfunction "2_2") (pintype "passive"))
    )
    (net (code "156") (name "/SDRAM_D28") (class "Default")
      (node (ref "R714") (pin "2") (pinfunction "2_2") (pintype "passive"))
    )
    (net (code "157") (name "/SDRAM_D29") (class "Default")
      (node (ref "R716") (pin "2") (pinfunction "2_2") (pintype "passive"))
    )
    (net (code "158") (name "/SDRAM_D30") (class "Default")
      (node (ref "R722") (pin "2") (pinfunction "2_2") (pintype "passive"))
    )
    (net (code "159") (name "/SDRAM_D31") (class "Default")
      (node (ref "R725") (pin "2") (pinfunction "2_2") (pintype "passive"))
    )
    (net (code "161") (name "/SDRAM_DM0") (class "Default")
      (node (ref "R733") (pin "2") (pinfunction "2_2") (pintype "passive"))
    )
    (net (code "162") (name "/SDRAM_DM1") (class "Default")
      (node (ref "R735") (pin "2") (pinfunction "2_2") (pintype "passive"))
    )
    (net (code "163") (name "/SDRAM_DM2") (class "Default")
      (node (ref "R710") (pin "2") (pinfunction "2_2") (pintype "passive"))
    )
    (net (code "164") (name "/SDRAM_DM3") (class "Default")
      (node (ref "R713") (pin "2") (pinfunction "2_2") (pintype "passive"))
    )
    (net (code "166") (name "/SDRAM_RAS") (class "Default")
      (node (ref "R778") (pin "2") (pinfunction "2_2") (pintype "passive"))
    )
    (net (code "167") (name "/SDRAM_WE") (class "Default")
      (node (ref "R762") (pin "2") (pinfunction "2_2") (pintype "passive"))
    )
    (net (code "168") (name "/SWCLK") (class "Default")
      (node (ref "U600") (pin "B14") (pinfunction "PA14(JTCK/SWCLK)_B14") (pintype "passive"))
    )
    (net (code "169") (name "/SWDIO") (class "Default")
      (node (ref "R728") (pin "2") (pinfunction "2_2") (pintype "passive"))
    )
    (net (code "170") (name "/SWO") (class "Default")
      (node (ref "R738") (pin "2") (pinfunction "2_2") (pintype "passive"))
    )
    (net (code "171") (name "/T0") (class "Default")
      (node (ref "R739") (pin "2") (pinfunction "2_2") (pintype "passive"))
    )
    (net (code "172") (name "/T1") (class "Default")
      (node (ref "R740") (pin "2") (pinfunction "2_2") (pintype "passive"))
    )
    (net (code "173") (name "/T2") (class "Default")
      (node (ref "R742") (pin "2") (pinfunction "2_2") (pintype "passive"))
    )
    (net (code "174") (name "/T3") (class "Default")
      (node (ref "R744") (pin "2") (pinfunction "2_2") (pintype "passive"))
    )
    (net (code "175") (name "/TCLK") (class "Default")
      (node (ref "R737") (pin "2") (pinfunction "2_2") (pintype "passive"))
    )
    (net (code "176") (name "/TMP_CH0") (class "Default")
      (node (ref "U600") (pin "M4") (pinfunction "PC3_M4") (pintype "passive"))
      (node (ref "U600") (pin "N3") (pinfunction "PA2_N3") (pintype "passive"))
    )
    (net (code "178") (name "/TO_DBG0") (class "Default")
      (node (ref "U600") (pin "R15") (pinfunction "PD11_R15") (pintype "passive"))
    )
    (net (code "179") (name "/TO_DBG1") (class "Default")
      (node (ref "U600") (pin "N14") (pinfunction "PJ7_N14") (pintype "passive"))
    )
    (net (code "180") (name "/TO_DBG2") (class "Default")
      (node (ref "U600") (pin "M14") (pinfunction "PJ9_M14") (pintype "passive"))
    )
    (net (code "181") (name "/TO_DBG3") (class "Default")
      (node (ref "U600") (pin "L14") (pinfunction "PJ10_L14") (pintype "passive"))
    )
    (net (code "182") (name "/TO_DRV_EN") (class "Default")
      (node (ref "U600") (pin "F16") (pinfunction "PG7_F16") (pintype "passive"))
      (node (ref "U701") (pin "2") (pinfunction "B_2") (pintype "passive"))
    )
    (net (code "183") (name "/WKUP") (class "Default")
      (node (ref "U600") (pin "E4") (pinfunction "PI8_E4") (pintype "passive"))
    )
    (net (code "200") (name "GND") (class "Default")
      (node (ref "C700") (pin "2") (pinfunction "2_2") (pintype "passive"))
      (node (ref "C701") (pin "2") (pinfunction "2_2") (pintype "passive"))
      (node (ref "C703") (pin "2") (pinfunction "2_2") (pintype "passive"))
      (node (ref "C704") (pin "2") (pinfunction "2_2") (pintype "passive"))
      (node (ref "C705") (pin "2") (pinfunction "2_2") (pintype "passive"))
      (node (ref "R785") (pin "1") (pinfunction "1_1") (pintype "passive"))
      (node (ref "U701") (pin "3") (pinfunction "GND_3") (pintype "passive"))
      (node (ref "Y700") (pin "2") (pinfunction "GND_2") (pintype "passive"))
      (node (ref "Y701") (pin "2") (pinfunction "GND_2") (pintype "passive"))
    )
    (net (code "201") (name "Net-(U600A-PA4)") (class "Default")
      (node (ref "R708") (pin "1") (pinfunction "1_1") (pintype "passive"))
      (node (ref "U600") (pin "U3") (pinfunction "PA4_U3") (pintype "passive"))
    )
    (net (code "202") (name "Net-(U600A-PA5)") (class "Default")
      (node (ref "R711") (pin "1") (pinfunction "1_1") (pintype "passive"))
      (node (ref "U600") (pin "T3") (pinfunction "PA5_T3") (pintype "passive"))
    )
    (net (code "203") (name "Net-(U600A-PA7)") (class "Default")
      (node (ref "R715") (pin "1") (pinfunction "1_1") (pintype "passive"))
      (node (ref "U600") (pin "R5") (pinfunction "PA7_R5") (pintype "passive"))
    )
    (net (code "204") (name "Net-(U600A-PA9)") (class "Default")
      (node (ref "R719") (pin "1") (pinfunction "1_1") (pintype "passive"))
      (node (ref "U600") (pin "D15") (pinfunction "PA9_D15") (pintype "passive"))
    )
    (net (code "205") (name "Net-(U600A-PA10)") (class "Default")
      (node (ref "R723") (pin "1") (pinfunction "1_1") (pintype "passive"))
      (node (ref "U600") (pin "D14") (pinfunction "PA10_D14") (pintype "passive"))
    )
    (net (code "206") (name "Net-(U600A-PA11)") (class "Default")
      (node (ref "R726") (pin "1") (pinfunction "1_1") (pintype "passive"))
      (node (ref "U600") (pin "E17") (pinfunction "PA11_E17") (pintype "passive"))
    )
    (net (code "207") (name "Net-(U600A-PA12)") (class "Default")
      (node (ref "R727") (pin "1") (pinfunction "1_1") (pintype "passive"))
      (node (ref "U600") (pin "E16") (pinfunction "PA12_E16") (pintype "passive"))
    )
    (net (code "208") (name "Net-(U600A-PA13(JTMS{slash}SWDIO))") (class "Default")
      (node (ref "R728") (pin "1") (pinfunction "1_1") (pintype "passive"))
      (node (ref "U600") (pin "C15") (pinfunction "PA13(JTMS/SWDIO)_C15") (pintype "passive"))
    )
    (net (code "209") (name "Net-(U600A-PB3(JTDO{slash}TRACESWO))") (class "Default")
      (node (ref "R738") (pin "1") (pinfunction "1_1") (pintype "passive"))
      (node (ref "U600") (pin "C6") (pinfunction "PB3(JTDO/TRACESWO)_C6") (pintype "passive"))
    )
    (net (code "210") (name "Net-(U600A-PB5)") (class "Default")
      (node (ref "R741") (pin "1") (pinfunction "1_1") (pintype "passive"))
      (node (ref "U600") (pin "A5") (pinfunction "PB5_A5") (pintype "passive"))
    )
    (net (code "211") (name "Net-(U600A-PB6)") (class "Default")
      (node (ref "R743") (pin "1") (pinfunction "1_1") (pintype "passive"))
      (node (ref "U600") (pin "B5") (pinfunction "PB6_B5") (pintype "passive"))
    )
    (net (code "212") (name "Net-(U600A-PC0)") (class "Default")
      (node (ref "R762") (pin "1") (pinfunction "1_1") (pintype "passive"))
      (node (ref "U600") (pin "L2") (pinfunction "PC0_L2") (pintype "passive"))
    )
    (net (code "213") (name "Net-(U600A-PC1)") (class "Default")
      (node (ref "R764") (pin "1") (pinfunction "1_1") (pintype "passive"))
      (node (ref "U600") (pin "M2") (pinfunction "PC1_M2") (pintype "passive"))
    )
    (net (code "214") (name "Net-(U600A-PC11)") (class "Default")
      (node (ref "R777") (pin "1") (pinfunction "1_1") (pintype "passive"))
      (node (ref "U600") (pin "B13") (pinfunction "PC11_B13") (pintype "passive"))
    )
    (net (code "215") (name "Net-(U600A-PC14-OSC32_IN)") (class "Default")
      (node (ref "R781") (pin "2") (pinfunction "2_2") (pintype "passive"))
      (node (ref "U600") (pin "C2") (pinfunction "PC14-OSC32_IN_C2") (pintype "passive"))
    )
    (net (code "216") (name "Net-(U600A-PD0)") (class "Default")
      (node (ref "R700") (pin "1") (pinfunction "1_1") (pintype "passive"))
      (node (ref "U600") (pin "D13") (pinfunction "PD0_D13") (pintype "passive"))
    )
    (net (code "217") (name "Net-(U600A-PD1)") (class "Default")
      (node (ref "R703") (pin "1") (pinfunction "1_1") (pintype "passive"))
      (node (ref "U600") (pin "E12") (pinfunction "PD1_E12") (pintype "passive"))
    )
    (net (code "218") (name "Net-(U600A-PD8)") (class "Default")
      (node (ref "R717") (pin "1") (pinfunction "1_1") (pintype "passive"))
      (node (ref "U600") (pin "U16") (pinfunction "PD8_U16") (pintype "passive"))
    )
    (net (code "219") (name "Net-(U600A-PD9)") (class "Default")
      (node (ref "R720") (pin "1") (pinfunction "1_1") (pintype "passive"))
      (node (ref "U600") (pin "T17") (pinfunction "PD9_T17") (pintype "passive"))
    )
    (net (code "220") (name "Net-(U600A-PD10)") (class "Default")
      (node (ref "R724") (pin "1") (pinfunction "1_1") (pintype "passive"))
      (node (ref "U600") (pin "T16") (pinfunction "PD10_T16") (pintype "passive"))
    )
    (net (code "221") (name "Net-(U600A-PD14)") (class "Default")
      (node (ref "R729") (pin "1") (pinfunction "1_1") (pintype "passive"))
      (node (ref "U600") (pin "P16") (pinfunction "PD14_P16") (pintype "passive"))
    )
    (net (code "222") (name "Net-(U600A-PD15)") (class "Default")
      (node (ref "R731") (pin "1") (pinfunction "1_1") (pintype "passive"))
      (node (ref "U600") (pin "P15") (pinfunction "PD15_P15") (pintype "passive"))
    )
    (net (code "223") (name "Net-(U600A-PE0)") (class "Default")
      (node (ref "R733") (pin "1") (pinfunction "1_1") (pintype "passive"))
      (node (ref "U600") (pin "C4") (pinfunction "PE0_C4") (pintype "passive"))
    )
    (net (code "224") (name "Net-(U600A-PE1)") (class "Default")
      (node (ref "R735") (pin "1") (pinfunction "1_1") (pintype "passive"))
      (node (ref "U600") (pin "B4") (pinfunction "PE1_B4") (pintype "passive"))
    )
    (net (code "225") (name "Net-(U600A-PE2)") (class "Default")
      (node (ref "R737") (pin "1") (pinfunction "1_1") (pintype "passive"))
      (node (ref "U600") (pin "C3") (pinfunction "PE2_C3") (pintype "passive"))
    )
    (net (code "226") (name "Net-(U600A-PE3)") (class "Default")
      (node (ref "R739") (pin "1") (pinfunction "1_1") (pintype "passive"))
      (node (ref "U600") (pin "D3") (pinfunction "PE3_D3") (pintype "passive"))
    )
    (net (code "227") (name "Net-(U600A-PE4)") (class "Default")
      (node (ref "R740") (pin "1") (pinfunction "1_1") (pintype "passive"))
      (node (ref "U600") (pin "D2") (pinfunction "PE4_D2") (pintype "passive"))
    )
    (net (code "228") (name "Net-(U600A-PE5)") (class "Default")
      (node (ref "R742") (pin "1") (pinfunction "1_1") (pintype "passive"))
      (node (ref "U600") (pin "D1") (pinfunction "PE5_D1") (pintype "passive"))
    )
    (net (code "229") (name "Net-(U600A-PE6)") (class "Default")
      (node (ref "R744") (pin "1") (pinfunction "1_1") (pintype "passive"))
      (node (ref "U600") (pin "E5") (pinfunction "PE6_E5") (pintype "passive"))
    )
    (net (code "230") (name "Net-(U600A-PE7)") (class "Default")
      (node (ref "R746") (pin "1") (pinfunction "1_1") (pintype "passive"))
      (node (ref "U600") (pin "U9") (pinfunction "PE7_U9") (pintype "passive"))
    )
    (net (code "231") (name "Net-(U600A-PE8)") (class "Default")
      (node (ref "R748") (pin "1") (pinfunction "1_1") (pintype "passive"))
      (node (ref "U600") (pin "T9") (pinfunction "PE8_T9") (pintype "passive"))
    )
    (net (code "232") (name "Net-(U600A-PE9)") (class "Default")
      (node (ref "R750") (pin "1") (pinfunction "1_1") (pintype "passive"))
      (node (ref "U600") (pin "P9") (pinfunction "PE9_P9") (pintype "passive"))
    )
    (net (code "233") (name "Net-(U600A-PE10)") (class "Default")
      (node (ref "R752") (pin "1") (pinfunction "1_1") (pintype "passive"))
      (node (ref "U600") (pin "N9") (pinfunction "PE10_N9") (pintype "passive"))
    )
    (net (code "234") (name "Net-(U600A-PE11)") (class "Default")
      (node (ref "R754") (pin "1") (pinfunction "1_1") (pintype "passive"))
      (node (ref "U600") (pin "P10") (pinfunction "PE11_P10") (pintype "passive"))
    )
    (net (code "235") (name "Net-(U600A-PE12)") (class "Default")
      (node (ref "R756") (pin "1") (pinfunction "1_1") (pintype "passive"))
      (node (ref "U600") (pin "R10") (pinfunction "PE12_R10") (pintype "passive"))
    )
    (net (code "236") (name "Net-(U600A-PE13)") (class "Default")
      (node (ref "R758") (pin "1") (pinfunction "1_1") (pintype "passive"))
      (node (ref "U600") (pin "T10") (pinfunction "PE13_T10") (pintype "passive"))
    )
    (net (code "237") (name "Net-(U600A-PE14)") (class "Default")
      (node (ref "R760") (pin "1") (pinfunction "1_1") (pintype "passive"))
      (node (ref "U600") (pin "U10") (pinfunction "PE14_U10") (pintype "passive"))
    )
    (net (code "238") (name "Net-(U600A-PE15)") (class "Default")
      (node (ref "R761") (pin "1") (pinfunction "1_1") (pintype "passive"))
      (node (ref "U600") (pin "R11") (pinfunction "PE15_R11") (pintype "passive"))
    )
    (net (code "239") (name "Net-(U600A-PF0)") (class "Default")
      (node (ref "R763") (pin "1") (pinfunction "1_1") (pintype "passive"))
      (node (ref "U600") (pin "G4") (pinfunction "PF0_G4") (pintype "passive"))
    )
    (net (code "240") (name "Net-(U600A-PF1)") (class "Default")
      (node (ref "R765") (pin "1") (pinfunction "1_1") (pintype "passive"))
      (node (ref "U600") (pin "G3") (pinfunction "PF1_G3") (pintype "passive"))
    )
    (net (code "241") (name "Net-(U600A-PF2)") (class "Default")
      (node (ref "R766") (pin "1") (pinfunction "1_1") (pintype "passive"))
      (node (ref "U600") (pin "G1") (pinfunction "PF2_G1") (pintype "passive"))
    )
    (net (code "242") (name "Net-(U600A-PF3)") (class "Default")
      (node (ref "R767") (pin "1") (pinfunction "1_1") (pintype "passive"))
      (node (ref "U600") (pin "H4") (pinfunction "PF3_H4") (pintype "passive"))
    )
    (net (code "243") (name "Net-(U600A-PF4)") (class "Default")
      (node (ref "R768") (pin "1") (pinfunction "1_1") (pintype "passive"))
      (node (ref "U600") (pin "J5") (pinfunction "PF4_J5") (pintype "passive"))
    )
    (net (code "244") (name "Net-(U600A-PF5)") (class "Default")
      (node (ref "R769") (pin "1") (pinfunction "1_1") (pintype "passive"))
      (node (ref "U600") (pin "J4") (pinfunction "PF5_J4") (pintype "passive"))
    )
    (net (code "245") (name "Net-(U600A-PF6)") (class "Default")
      (node (ref "R770") (pin "1") (pinfunction "1_1") (pintype "passive"))
      (node (ref "U600") (pin "K2") (pinfunction "PF6_K2") (pintype "passive"))
    )
    (net (code "246") (name "Net-(U600A-PF7)") (class "Default")
      (node (ref "R771") (pin "1") (pinfunction "1_1") (pintype "passive"))
      (node (ref "U600") (pin "K3") (pinfunction "PF7_K3") (pintype "passive"))
    )
    (net (code "247") (name "Net-(U600A-PF8)") (class "Default")
      (node (ref "R773") (pin "1") (pinfunction "1_1") (pintype "passive"))
      (node (ref "U600") (pin "K4") (pinfunction "PF8_K4") (pintype "passive"))
    )
    (net (code "248") (name "Net-(U600A-PF9)") (class "Default")
      (node (ref "R774") (pin "1") (pinfunction "1_1") (pintype "passive"))
      (node (ref "U600") (pin "L4") (pinfunction "PF9_L4") (pintype "passive"))
    )
    (net (code "249") (name "Net-(U600A-PF10)") (class "Default")
      (node (ref "R776") (pin "1") (pinfunction "1_1") (pintype "passive"))
      (node (ref "U600") (pin "L3") (pinfunction "PF10_L3") (pintype "passive"))
    )
    (net (code "250") (name "Net-(U600A-PF11)") (class "Default")
      (node (ref "R778") (pin "1") (pinfunction "1_1") (pintype "passive"))
      (node (ref "U600") (pin "T7") (pinfunction "PF11_T7") (pintype "passive"))
    )
    (net (code "251") (name "Net-(U600A-PF12)") (class "Default")
      (node (ref "R779") (pin "1") (pinfunction "1_1") (pintype "passive"))
      (node (ref "U600") (pin "R7") (pinfunction "PF12_R7") (pintype "passive"))
    )
    (net (code "252") (name "Net-(U600A-PF13)") (class "Default")
      (node (ref "R780") (pin "1") (pinfunction "1_1") (pintype "passive"))
      (node (ref "U600") (pin "P7") (pinfunction "PF13_P7") (pintype "passive"))
    )
    (net (code "253") (name "Net-(U600A-PF14)") (class "Default")
      (node (ref "R782") (pin "1") (pinfunction "1_1") (pintype "passive"))
      (node (ref "U600") (pin "P8") (pinfunction "PF14_P8") (pintype "passive"))
    )
    (net (code "254") (name "Net-(U600A-PF15)") (class "Default")
      (node (ref "R783") (pin "1") (pinfunction "1_1") (pintype "passive"))
      (node (ref "U600") (pin "R9") (pinfunction "PF15_R9") (pintype "passive"))
    )
    (net (code "255") (name "Net-(U600B-PG0)") (class "Default")
      (node (ref "R701") (pin "1") (pinfunction "1_1") (pintype "passive"))
      (node (ref "U600") (pin "T8") (pinfunction "PG0_T8") (pintype "passive"))
    )
    (net (code "256") (name "Net-(U600B-PG1)") (class "Default")
      (node (ref "R704") (pin "1") (pinfunction "1_1") (pintype "passive"))
      (node (ref "U600") (pin "U8") (pinfunction "PG1_U8") (pintype "passive"))
    )
    (net (code "257") (name "Net-(U600B-PG4)") (class "Default")
      (node (ref "R709") (pin "1") (pinfunction "1_1") (pintype "passive"))
      (node (ref "U600") (pin "H14") (pinfunction "PG4_H14") (pintype "passive"))
    )
    (net (code "258") (name "Net-(U600B-PG5)") (class "Default")
      (node (ref "R712") (pin "1") (pinfunction "1_1") (pintype "passive"))
      (node (ref "U600") (pin "G14") (pinfunction "PG5_G14") (pintype "passive"))
    )
    (net (code "259") (name "Net-(U600B-PG8)") (class "Default")
      (node (ref "R718") (pin "1") (pinfunction "1_1") (pintype "passive"))
      (node (ref "U600") (pin "F15") (pinfunction "PG8_F15") (pintype "passive"))
    )
    (net (code "260") (name "Net-(U600B-PG9)") (class "Default")
      (node (ref "R721") (pin "1") (pinfunction "1_1") (pintype "passive"))
      (node (ref "U600") (pin "A10") (pinfunction "PG9_A10") (pintype "passive"))
    )
    (net (code "261") (name "Net-(U600B-PG14)") (class "Default")
      (node (ref "R730") (pin "1") (pinfunction "1_1") (pintype "passive"))
      (node (ref "U600") (pin "D8") (pinfunction "PG14_D8") (pintype "passive"))
    )
    (net (code "262") (name "Net-(U600B-PG15)") (class "Default")
      (node (ref "R732") (pin "1") (pinfunction "1_1") (pintype "passive"))
      (node (ref "U600") (pin "D6") (pinfunction "PG15_D6") (pintype "passive"))
    )
    (net (code "263") (name "Net-(U600B-PH0-OSCIN)") (class "Default")
      (node (ref "R775") (pin "1") (pinfunction "1_1") (pintype "passive"))
      (node (ref "U600") (pin "J2") (pinfunction "PH0-OSCIN_J2") (pintype "passive"))
    )
    (net (code "264") (name "Net-(U600B-PH2)") (class "Default")
      (node (ref "R734") (pin "1") (pinfunction "1_1") (pintype "passive"))
      (node (ref "U600") (pin "N2") (pinfunction "PH2_N2") (pintype "passive"))
    )
    (net (code "265") (name "Net-(U600B-PH3)") (class "Default")
      (node (ref "R736") (pin "1") (pinfunction "1_1") (pintype "passive"))
      (node (ref "U600") (pin "P2") (pinfunction "PH3_P2") (pintype "passive"))
    )
    (net (code "266") (name "Net-(U600B-PH8)") (class "Default")
      (node (ref "R745") (pin "1") (pinfunction "1_1") (pintype "passive"))
      (node (ref "U600") (pin "T13") (pinfunction "PH8_T13") (pintype "passive"))
    )
    (net (code "267") (name "Net-(U600B-PH9)") (class "Default")
      (node (ref "R747") (pin "1") (pinfunction "1_1") (pintype "passive"))
      (node (ref "U600") (pin "R13") (pinfunction "PH9_R13") (pintype "passive"))
    )
    (net (code "268") (name "Net-(U600B-PH10)") (class "Default")
      (node (ref "R749") (pin "1") (pinfunction "1_1") (pintype "passive"))
      (node (ref "U600") (pin "P13") (pinfunction "PH10_P13") (pintype "passive"))
    )
    (net (code "269") (name "Net-(U600B-PH11)") (class "Default")
      (node (ref "R751") (pin "1") (pinfunction "1_1") (pintype "passive"))
      (node (ref "U600") (pin "P14") (pinfunction "PH11_P14") (pintype "passive"))
    )
    (net (code "270") (name "Net-(U600B-PH12)") (class "Default")
      (node (ref "R753") (pin "1") (pinfunction "1_1") (pintype "passive"))
      (node (ref "U600") (pin "R14") (pinfunction "PH12_R14") (pintype "passive"))
    )
    (net (code "271") (name "Net-(U600B-PH13)") (class "Default")
      (node (ref "R755") (pin "1") (pinfunction "1_1") (pintype "passive"))
      (node (ref "U600") (pin "D16") (pinfunction "PH13_D16") (pintype "passive"))
    )
    (net (code "272") (name "Net-(U600B-PH14)") (class "Default")
      (node (ref "R757") (pin "1") (pinfunction "1_1") (pintype "passive"))
      (node (ref "U600") (pin "B17") (pinfunction "PH14_B17") (pintype "passive"))
    )
    (net (code "273") (name "Net-(U600B-PH15)") (class "Default")
      (node (ref "R759") (pin "1") (pinfunction "1_1") (pintype "passive"))
      (node (ref "U600") (pin "B16") (pinfunction "PH15_B16") (pintype "passive"))
    )
    (net (code "274") (name "Net-(U600B-PI0)") (class "Default")
      (node (ref "R702") (pin "1") (pinfunction "1_1") (pintype "passive"))
      (node (ref "U600") (pin "A16") (pinfunction "PI0_A16") (pintype "passive"))
    )
    (net (code "275") (name "Net-(U600B-PI1)") (class "Default")
      (node (ref "R705") (pin "1") (pinfunction "1_1") (pintype "passive"))
      (node (ref "U600") (pin "A15") (pinfunction "PI1_A15") (pintype "passive"))
    )
    (net (code "276") (name "Net-(U600B-PI2)") (class "Default")
      (node (ref "R706") (pin "1") (pinfunction "1_1") (pintype "passive"))
      (node (ref "U600") (pin "B15") (pinfunction "PI2_B15") (pintype "passive"))
    )
    (net (code "277") (name "Net-(U600B-PI3)") (class "Default")
      (node (ref "R707") (pin "1") (pinfunction "1_1") (pintype "passive"))
      (node (ref "U600") (pin "C14") (pinfunction "PI3_C14") (pintype "passive"))
    )
    (net (code "278") (name "Net-(U600B-PI4)") (class "Default")
      (node (ref "R710") (pin "1") (pinfunction "1_1") (pintype "passive"))
      (node (ref "U600") (pin "A4") (pinfunction "PI4_A4") (pintype "passive"))
    )
    (net (code "279") (name "Net-(U600B-PI5)") (class "Default")
      (node (ref "R713") (pin "1") (pinfunction "1_1") (pintype "passive"))
      (node (ref "U600") (pin "A3") (pinfunction "PI5_A3") (pintype "passive"))
    )
    (net (code "280") (name "Net-(U600B-PI6)") (class "Default")
      (node (ref "R714") (pin "1") (pinfunction "1_1") (pintype "passive"))
      (node (ref "U600") (pin "A2") (pinfunction "PI6_A2") (pintype "passive"))
    )
    (net (code "281") (name "Net-(U600B-PI7)") (class "Default")
      (node (ref "R716") (pin "1") (pinfunction "1_1") (pintype "passive"))
      (node (ref "U600") (pin "B3") (pinfunction "PI7_B3") (pintype "passive"))
    )
    (net (code "282") (name "Net-(U600B-PI9)") (class "Default")
      (node (ref "R722") (pin "1") (pinfunction "1_1") (pintype "passive"))
      (node (ref "U600") (pin "E2") (pinfunction "PI9_E2") (pintype "passive"))
    )
    (net (code "283") (name "Net-(U600B-PI10)") (class "Default")
      (node (ref "R725") (pin "1") (pinfunction "1_1") (pintype "passive"))
      (node (ref "U600") (pin "F3") (pinfunction "PI10_F3") (pintype "passive"))
    )
    (net (code "284") (name "Net-(Y700-ED)") (class "Default")
      (node (ref "R786") (pin "2") (pinfunction "2_2") (pintype "passive"))
      (node (ref "Y700") (pin "1") (pinfunction "ED_1") (pintype "passive"))
    )
    (net (code "285") (name "Net-(Y700-OUT)") (class "Default")
      (node (ref "R775") (pin "2") (pinfunction "2_2") (pintype "passive"))
      (node (ref "Y700") (pin "3") (pinfunction "OUT_3") (pintype "passive"))
    )
    (net (code "286") (name "Net-(Y701-ED)") (class "Default")
      (node (ref "R787") (pin "2") (pinfunction "2_2") (pintype "passive"))
      (node (ref "Y701") (pin "1") (pinfunction "ED_1") (pintype "passive"))
    )
    (net (code "287") (name "Net-(Y701-OUT)") (class "Default")
      (node (ref "R781") (pin "1") (pinfunction "1_1") (pintype "passive"))
      (node (ref "Y701") (pin "3") (pinfunction "OUT_3") (pintype "passive"))
    )
    (net (code "288") (name "VMCU") (class "Default")
      (node (ref "C702") (pin "2") (pinfunction "2_2") (pintype "passive"))
      (node (ref "C703") (pin "1") (pinfunction "1_1") (pintype "passive"))
      (node (ref "C704") (pin "1") (pinfunction "1_1") (pintype "passive"))
      (node (ref "C705") (pin "1") (pinfunction "1_1") (pintype "passive"))
      (node (ref "R772") (pin "1") (pinfunction "1_1") (pintype "passive"))
      (node (ref "R784") (pin "2") (pinfunction "2_2") (pintype "passive"))
      (node (ref "R786") (pin "1") (pinfunction "1_1") (pintype "passive"))
      (node (ref "R787") (pin "1") (pinfunction "1_1") (pintype "passive"))
      (node (ref "U701") (pin "5") (pinfunction "VCC_5") (pintype "passive"))
      (node (ref "Y700") (pin "4") (pinfunction "VDD_4") (pintype "passive"))
      (node (ref "Y701") (pin "4") (pinfunction "VDD_4") (pintype "passive"))
    )
    (net (code "289") (name "unconnected-(U600A-PB2-PadR6)") (class "Default")
      (node (ref "U600") (pin "R6") (pinfunction "PB2_R6") (pintype "passive+no_connect"))
    )
    (net (code "290") (name "unconnected-(U600A-PB7-PadC5)") (class "Default")
      (node (ref "U600") (pin "C5") (pinfunction "PB7_C5") (pintype "passive+no_connect"))
    )
    (net (code "291") (name "unconnected-(U600A-PB12-PadT14)") (class "Default")
      (node (ref "U600") (pin "T14") (pinfunction "PB12_T14") (pintype "passive+no_connect"))
    )
    (net (code "292") (name "unconnected-(U600A-PB13-PadU14)") (class "Default")
      (node (ref "U600") (pin "U14") (pinfunction "PB13_U14") (pintype "passive+no_connect"))
    )
    (net (code "293") (name "unconnected-(U600A-PC8-PadE13)") (class "Default")
      (node (ref "U600") (pin "E13") (pinfunction "PC8_E13") (pintype "passive+no_connect"))
    )
    (net (code "294") (name "unconnected-(U600A-PC10-PadA13)") (class "Default")
      (node (ref "U600") (pin "A13") (pinfunction "PC10_A13") (pintype "passive+no_connect"))
    )
    (net (code "295") (name "unconnected-(U600A-PC13-PadE3)") (class "Default")
      (node (ref "U600") (pin "E3") (pinfunction "PC13_E3") (pintype "passive+no_connect"))
    )
    (net (code "296") (name "unconnected-(U600A-PC15-OSC32_OUT-PadC1)") (class "Default")
      (node (ref "U600") (pin "C1") (pinfunction "PC15-OSC32_OUT_C1") (pintype "passive+no_connect"))
    )
    (net (code "297") (name "unconnected-(U600A-PD4-PadA12)") (class "Default")
      (node (ref "U600") (pin "A12") (pinfunction "PD4_A12") (pintype "passive+no_connect"))
    )
    (net (code "298") (name "unconnected-(U600B-PC2_C-PadR1)") (class "Default")
      (node (ref "U600") (pin "R1") (pinfunction "PC2_C_R1") (pintype "passive+no_connect"))
    )
    (net (code "299") (name "unconnected-(U600B-PC3_C-PadR2)") (class "Default")
      (node (ref "U600") (pin "R2") (pinfunction "PC3_C_R2") (pintype "passive+no_connect"))
    )
    (net (code "300") (name "unconnected-(U600B-PG3-PadH15)") (class "Default")
      (node (ref "U600") (pin "H15") (pinfunction "PG3_H15") (pintype "passive"))
    )
    (net (code "301") (name "unconnected-(U600B-PH1-OSCOUT-PadJ1)") (class "Default")
      (node (ref "U600") (pin "J1") (pinfunction "PH1-OSCOUT_J1") (pintype "passive+no_connect"))
    )
    (net (code "302") (name "unconnected-(U600B-PH6-PadT11)") (class "Default")
      (node (ref "U600") (pin "T11") (pinfunction "PH6_T11") (pintype "passive+no_connect"))
    )
    (net (code "303") (name "unconnected-(U600B-PH7-PadU13)") (class "Default")
      (node (ref "U600") (pin "U13") (pinfunction "PH7_U13") (pintype "passive+no_connect"))
    )
    (net (code "304") (name "unconnected-(U600B-PJ5-PadR12)") (class "Default")
      (node (ref "U600") (pin "R12") (pinfunction "PJ5_R12") (pintype "passive+no_connect"))
    )
    (net (code "305") (name "unconnected-(U600B-PJ6-PadN15)") (class "Default")
      (node (ref "U600") (pin "N15") (pinfunction "PJ6_N15") (pintype "passive+no_connect"))
    )
    (net (code "306") (name "unconnected-(U600B-PJ8-PadN13)") (class "Default")
      (node (ref "U600") (pin "N13") (pinfunction "PJ8_N13") (pintype "passive+no_connect"))
    )
  )
)
